# S01.net
KiCad netlist of a schematic drawn in Altium Designer
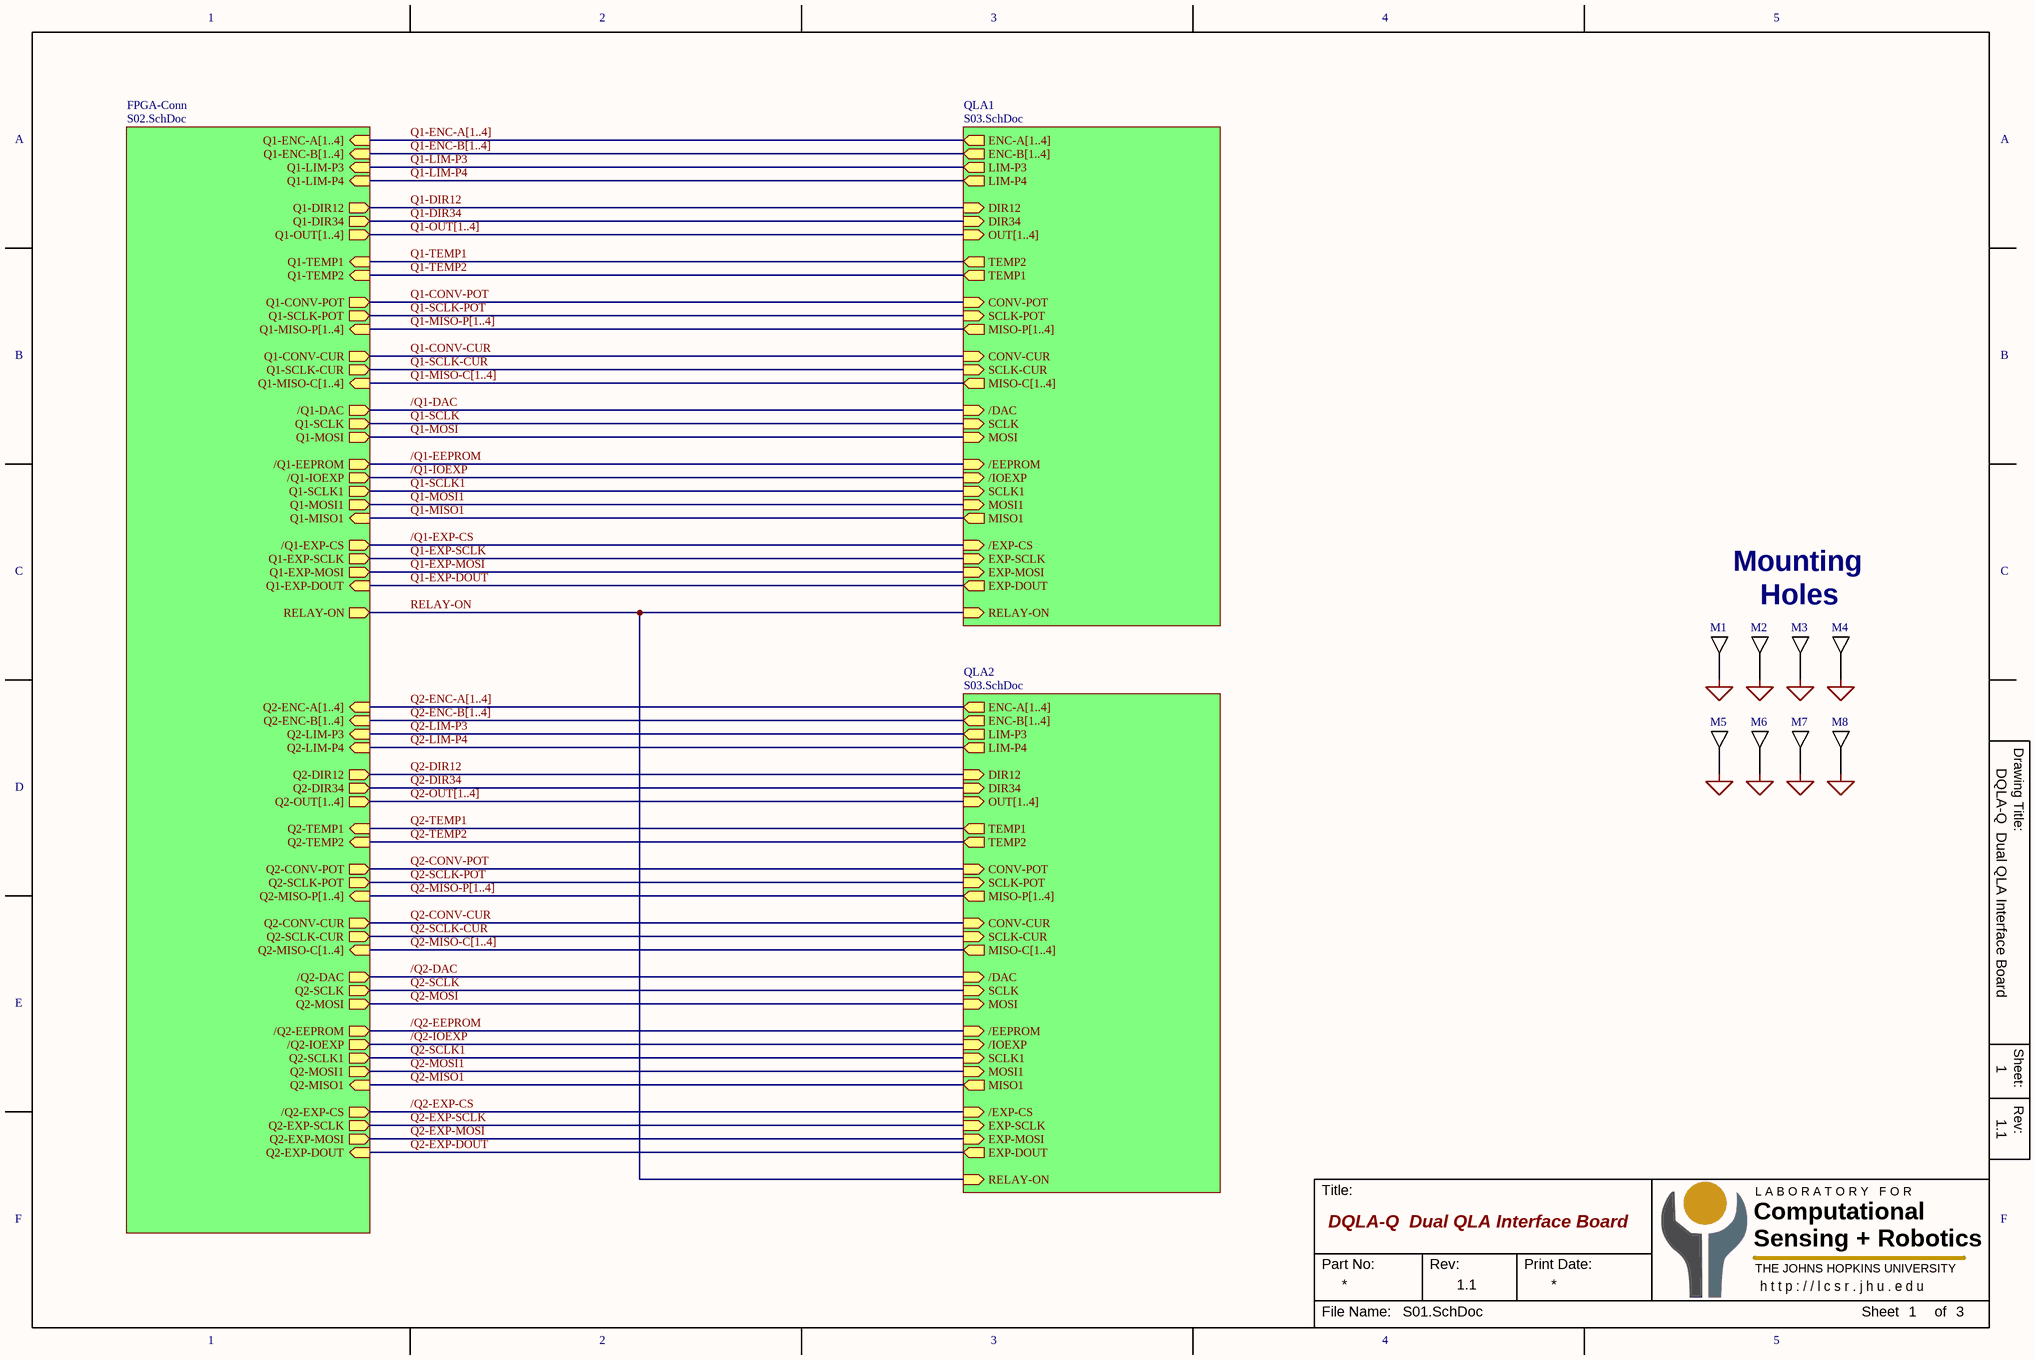
[diagram p0: S01.SchDoc]

(export (version "E")
  (design (tool "Eeschema 10.0.6"))
  (components
    (comp (ref "M1")
      (value "MHOLE")
      (footprint "MHOLE4")
      (description "Mounting Hole")
      (libsource (lib "LibJHU") (part "MHOLE"))
    )
    (comp (ref "M2")
      (value "MHOLE")
      (footprint "MHOLE4")
      (description "Mounting Hole")
      (libsource (lib "LibJHU") (part "MHOLE"))
    )
    (comp (ref "M3")
      (value "MHOLE")
      (footprint "MHOLE4")
      (description "Mounting Hole")
      (libsource (lib "LibJHU") (part "MHOLE"))
    )
    (comp (ref "M4")
      (value "MHOLE")
      (footprint "MHOLE4")
      (description "Mounting Hole")
      (libsource (lib "LibJHU") (part "MHOLE"))
    )
    (comp (ref "M5")
      (value "MHOLE")
      (footprint "MHOLE4")
      (description "Mounting Hole")
      (libsource (lib "LibJHU") (part "MHOLE"))
    )
    (comp (ref "M6")
      (value "MHOLE")
      (footprint "MHOLE4")
      (description "Mounting Hole")
      (libsource (lib "LibJHU") (part "MHOLE"))
    )
    (comp (ref "M7")
      (value "MHOLE")
      (footprint "MHOLE4")
      (description "Mounting Hole")
      (libsource (lib "LibJHU") (part "MHOLE"))
    )
    (comp (ref "M8")
      (value "MHOLE")
      (footprint "MHOLE4")
      (description "Mounting Hole")
      (libsource (lib "LibJHU") (part "MHOLE"))
    )
  )
  (nets
    (net (code "96") (name "GND") (class "Default")
      (node (ref "M1") (pin "1") (pinfunction "1_1") (pintype "passive"))
      (node (ref "M2") (pin "1") (pinfunction "1_1") (pintype "passive"))
      (node (ref "M3") (pin "1") (pinfunction "1_1") (pintype "passive"))
      (node (ref "M4") (pin "1") (pinfunction "1_1") (pintype "passive"))
      (node (ref "M5") (pin "1") (pinfunction "1_1") (pintype "passive"))
      (node (ref "M6") (pin "1") (pinfunction "1_1") (pintype "passive"))
      (node (ref "M7") (pin "1") (pinfunction "1_1") (pintype "passive"))
      (node (ref "M8") (pin "1") (pinfunction "1_1") (pintype "passive"))
    )
  )
)
